# Pacman.net
KiCad netlist of a schematic drawn in EAGLE
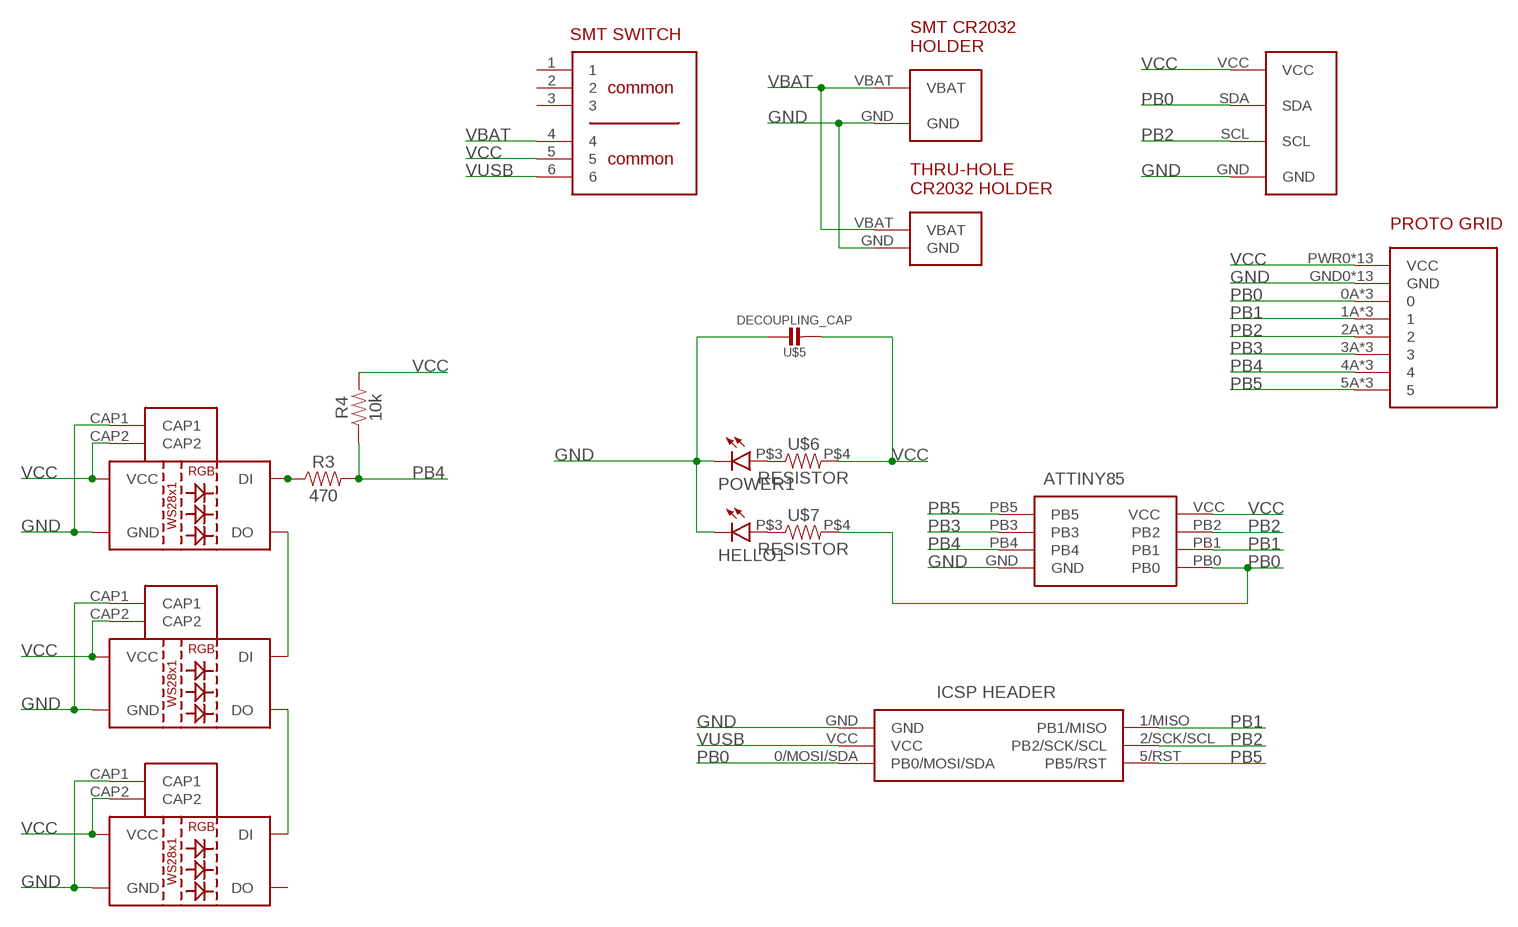
[diagram p0: schematic, sheet 1]

(export (version "E")
  (design (tool "Eeschema 10.0.6"))
  (components
    (comp (ref "D4")
      (value "WS2812B")
      (footprint "eagle-import:WS2812B")
      (libsource (lib "eagle-import") (part "WS2812B"))
    )
    (comp (ref "D5")
      (value "WS2812B")
      (footprint "eagle-import:WS2812B")
      (libsource (lib "eagle-import") (part "WS2812B"))
    )
    (comp (ref "D6")
      (value "WS2812B")
      (footprint "eagle-import:WS2812B")
      (libsource (lib "eagle-import") (part "WS2812B"))
    )
    (comp (ref "HELLO1")
      (value "LED3MM")
      (footprint "eagle-import:LED3MM")
      (libsource (lib "eagle-import") (part "LED3MM"))
    )
    (comp (ref "IC2")
      (value "ATTINY85-20SU")
      (footprint "eagle-import:SOT127P798X216-8N")
      (fields (field (name "RS_PART_NUMBER") "1331674"))
      (libsource (lib "eagle-import") (part "ATTINY85-20SU"))
    )
    (comp (ref "J2")
      (value "M20-9980346")
      (footprint "eagle-import:HDRV6W64P254_2X3_762X508X868P")
      (fields (field (name "RS_PART_NUMBER") "7457046P"))
      (libsource (lib "eagle-import") (part "M20-9980346"))
    )
    (comp (ref "POWER1")
      (value "LED3MM")
      (footprint "eagle-import:LED3MM")
      (libsource (lib "eagle-import") (part "LED3MM"))
    )
    (comp (ref "R3")
      (value "470")
      (footprint "eagle-import:0603")
      (libsource (lib "eagle-import") (part "470OHM-0603-1/10W-1%"))
    )
    (comp (ref "R4")
      (value "10k")
      (footprint "eagle-import:0603")
      (libsource (lib "eagle-import") (part "10KOHM-0603-1/10W-1%"))
    )
    (comp (ref "U$5")
      (value "DECOUPLING_CAP")
      (footprint "eagle-import:DECOUPLING_CAP")
      (libsource (lib "eagle-import") (part "DECOUPLING_CAP"))
    )
    (comp (ref "U$6")
      (value "RESISTOR")
      (footprint "eagle-import:AXIAL-0.3")
      (libsource (lib "eagle-import") (part "RESISTOR"))
    )
    (comp (ref "U$7")
      (value "RESISTOR")
      (footprint "eagle-import:AXIAL-0.3")
      (libsource (lib "eagle-import") (part "RESISTOR"))
    )
    (comp (ref "U$8")
      (value "SMT-SWITCH")
      (footprint "eagle-import:SMT-SWITCH")
      (libsource (lib "eagle-import") (part "SMT-SWITCH"))
    )
    (comp (ref "U$9")
      (value "PROTO")
      (footprint "eagle-import:PROTO")
      (libsource (lib "eagle-import") (part "PROTO"))
    )
    (comp (ref "U$10")
      (value "SMT-BATTERY-HOLDER")
      (footprint "eagle-import:SMT-CR-HOLDER")
      (libsource (lib "eagle-import") (part "SMT-BATTERY-HOLDER"))
    )
    (comp (ref "U$11")
      (value "THRU-CR-HOLDER")
      (footprint "eagle-import:THRU-CR-HOLDER")
      (libsource (lib "eagle-import") (part "THRU-CR-HOLDER"))
    )
    (comp (ref "U$12")
      (value "I2C-PADS")
      (footprint "eagle-import:I2C-PADS")
      (libsource (lib "eagle-import") (part "I2C-PADS"))
    )
  )
  (nets
    (net (code "1") (name "/GND") (class "Default")
      (node (ref "D4") (pin "CAP1") (pinfunction "CAP1_CAP1") (pintype "bidirectional"))
      (node (ref "D4") (pin "GND") (pinfunction "GND_GND") (pintype "bidirectional"))
      (node (ref "D5") (pin "CAP1") (pinfunction "CAP1_CAP1") (pintype "bidirectional"))
      (node (ref "D5") (pin "GND") (pinfunction "GND_GND") (pintype "bidirectional"))
      (node (ref "D6") (pin "CAP1") (pinfunction "CAP1_CAP1") (pintype "bidirectional"))
      (node (ref "D6") (pin "GND") (pinfunction "GND_GND") (pintype "bidirectional"))
      (node (ref "HELLO1") (pin "NEG") (pinfunction "NEG_NEG") (pintype "passive"))
      (node (ref "IC2") (pin "GND") (pinfunction "GND_GND") (pintype "bidirectional"))
      (node (ref "J2") (pin "GND") (pinfunction "GND_GND") (pintype "bidirectional"))
      (node (ref "POWER1") (pin "NEG") (pinfunction "NEG_NEG") (pintype "passive"))
      (node (ref "U$10") (pin "GND") (pinfunction "GND_GND") (pintype "bidirectional"))
      (node (ref "U$11") (pin "GND") (pinfunction "GND_GND") (pintype "bidirectional"))
      (node (ref "U$12") (pin "GND") (pinfunction "GND_GND") (pintype "bidirectional"))
      (node (ref "U$5") (pin "P$1") (pinfunction "1_P$1") (pintype "passive"))
      (node (ref "U$9") (pin "GND0") (pinfunction "GND_GND0") (pintype "bidirectional"))
      (node (ref "U$9") (pin "GND1") (pinfunction "GND_GND1") (pintype "bidirectional"))
      (node (ref "U$9") (pin "GND10") (pinfunction "GND_GND10") (pintype "bidirectional"))
      (node (ref "U$9") (pin "GND11") (pinfunction "GND_GND11") (pintype "bidirectional"))
      (node (ref "U$9") (pin "GND12") (pinfunction "GND_GND12") (pintype "bidirectional"))
      (node (ref "U$9") (pin "GND2") (pinfunction "GND_GND2") (pintype "bidirectional"))
      (node (ref "U$9") (pin "GND3") (pinfunction "GND_GND3") (pintype "bidirectional"))
      (node (ref "U$9") (pin "GND4") (pinfunction "GND_GND4") (pintype "bidirectional"))
      (node (ref "U$9") (pin "GND5") (pinfunction "GND_GND5") (pintype "bidirectional"))
      (node (ref "U$9") (pin "GND6") (pinfunction "GND_GND6") (pintype "bidirectional"))
      (node (ref "U$9") (pin "GND7") (pinfunction "GND_GND7") (pintype "bidirectional"))
      (node (ref "U$9") (pin "GND8") (pinfunction "GND_GND8") (pintype "bidirectional"))
      (node (ref "U$9") (pin "GND9") (pinfunction "GND_GND9") (pintype "bidirectional"))
    )
    (net (code "2") (name "/PB0") (class "Default")
      (node (ref "IC2") (pin "PB0") (pinfunction "PB0_PB0") (pintype "bidirectional"))
      (node (ref "J2") (pin "0/MOSI/SDA") (pinfunction "PB0/MOSI/SDA_0/MOSI/SDA") (pintype "bidirectional"))
      (node (ref "U$12") (pin "SDA") (pinfunction "SDA_SDA") (pintype "bidirectional"))
      (node (ref "U$7") (pin "P$4") (pinfunction "2_P$4") (pintype "passive"))
      (node (ref "U$9") (pin "0A") (pinfunction "0_0A") (pintype "bidirectional"))
      (node (ref "U$9") (pin "0B") (pinfunction "0_0B") (pintype "bidirectional"))
      (node (ref "U$9") (pin "0C") (pinfunction "0_0C") (pintype "bidirectional"))
    )
    (net (code "3") (name "/PB1") (class "Default")
      (node (ref "IC2") (pin "PB1") (pinfunction "PB1_PB1") (pintype "bidirectional"))
      (node (ref "J2") (pin "1/MISO") (pinfunction "PB1/MISO_1/MISO") (pintype "bidirectional"))
      (node (ref "U$9") (pin "1A") (pinfunction "1_1A") (pintype "bidirectional"))
      (node (ref "U$9") (pin "1B") (pinfunction "1_1B") (pintype "bidirectional"))
      (node (ref "U$9") (pin "1C") (pinfunction "1_1C") (pintype "bidirectional"))
    )
    (net (code "4") (name "/PB2") (class "Default")
      (node (ref "IC2") (pin "PB2") (pinfunction "PB2_PB2") (pintype "bidirectional"))
      (node (ref "J2") (pin "2/SCK/SCL") (pinfunction "PB2/SCK/SCL_2/SCK/SCL") (pintype "bidirectional"))
      (node (ref "U$12") (pin "SCL") (pinfunction "SCL_SCL") (pintype "bidirectional"))
      (node (ref "U$9") (pin "2A") (pinfunction "2_2A") (pintype "bidirectional"))
      (node (ref "U$9") (pin "2B") (pinfunction "2_2B") (pintype "bidirectional"))
      (node (ref "U$9") (pin "2C") (pinfunction "2_2C") (pintype "bidirectional"))
    )
    (net (code "5") (name "/PB3") (class "Default")
      (node (ref "IC2") (pin "PB3") (pinfunction "PB3_PB3") (pintype "bidirectional"))
      (node (ref "U$9") (pin "3A") (pinfunction "3_3A") (pintype "bidirectional"))
      (node (ref "U$9") (pin "3B") (pinfunction "3_3B") (pintype "bidirectional"))
      (node (ref "U$9") (pin "3C") (pinfunction "3_3C") (pintype "bidirectional"))
    )
    (net (code "6") (name "/PB4") (class "Default")
      (node (ref "IC2") (pin "PB4") (pinfunction "PB4_PB4") (pintype "bidirectional"))
      (node (ref "R3") (pin "2") (pinfunction "2_2") (pintype "passive"))
      (node (ref "R4") (pin "1") (pinfunction "1_1") (pintype "passive"))
      (node (ref "U$9") (pin "4A") (pinfunction "4_4A") (pintype "bidirectional"))
      (node (ref "U$9") (pin "4B") (pinfunction "4_4B") (pintype "bidirectional"))
      (node (ref "U$9") (pin "4C") (pinfunction "4_4C") (pintype "bidirectional"))
    )
    (net (code "7") (name "/PB5") (class "Default")
      (node (ref "IC2") (pin "PB5") (pinfunction "PB5_PB5") (pintype "bidirectional"))
      (node (ref "J2") (pin "5/RST") (pinfunction "PB5/RST_5/RST") (pintype "bidirectional"))
      (node (ref "U$9") (pin "5A") (pinfunction "5_5A") (pintype "bidirectional"))
      (node (ref "U$9") (pin "5B") (pinfunction "5_5B") (pintype "bidirectional"))
      (node (ref "U$9") (pin "5C") (pinfunction "5_5C") (pintype "bidirectional"))
    )
    (net (code "8") (name "/VBAT") (class "Default")
      (node (ref "U$10") (pin "VBAT") (pinfunction "VBAT_VBAT") (pintype "bidirectional"))
      (node (ref "U$11") (pin "VBAT") (pinfunction "VBAT_VBAT") (pintype "bidirectional"))
      (node (ref "U$8") (pin "4") (pinfunction "4_4") (pintype "bidirectional"))
    )
    (net (code "9") (name "/VCC") (class "Default")
      (node (ref "D4") (pin "CAP2") (pinfunction "CAP2_CAP2") (pintype "bidirectional"))
      (node (ref "D4") (pin "VCC") (pinfunction "VCC_VCC") (pintype "bidirectional"))
      (node (ref "D5") (pin "CAP2") (pinfunction "CAP2_CAP2") (pintype "bidirectional"))
      (node (ref "D5") (pin "VCC") (pinfunction "VCC_VCC") (pintype "bidirectional"))
      (node (ref "D6") (pin "CAP2") (pinfunction "CAP2_CAP2") (pintype "bidirectional"))
      (node (ref "D6") (pin "VCC") (pinfunction "VCC_VCC") (pintype "bidirectional"))
      (node (ref "IC2") (pin "VCC") (pinfunction "VCC_VCC") (pintype "bidirectional"))
      (node (ref "R4") (pin "2") (pinfunction "2_2") (pintype "passive"))
      (node (ref "U$12") (pin "VCC") (pinfunction "VCC_VCC") (pintype "bidirectional"))
      (node (ref "U$5") (pin "P$2") (pinfunction "2_P$2") (pintype "passive"))
      (node (ref "U$6") (pin "P$4") (pinfunction "2_P$4") (pintype "passive"))
      (node (ref "U$8") (pin "5") (pinfunction "5_5") (pintype "bidirectional"))
      (node (ref "U$9") (pin "PWR0") (pinfunction "VCC_PWR0") (pintype "bidirectional"))
      (node (ref "U$9") (pin "PWR1") (pinfunction "VCC_PWR1") (pintype "bidirectional"))
      (node (ref "U$9") (pin "PWR10") (pinfunction "VCC_PWR10") (pintype "bidirectional"))
      (node (ref "U$9") (pin "PWR11") (pinfunction "VCC_PWR11") (pintype "bidirectional"))
      (node (ref "U$9") (pin "PWR12") (pinfunction "VCC_PWR12") (pintype "bidirectional"))
      (node (ref "U$9") (pin "PWR2") (pinfunction "VCC_PWR2") (pintype "bidirectional"))
      (node (ref "U$9") (pin "PWR3") (pinfunction "VCC_PWR3") (pintype "bidirectional"))
      (node (ref "U$9") (pin "PWR4") (pinfunction "VCC_PWR4") (pintype "bidirectional"))
      (node (ref "U$9") (pin "PWR5") (pinfunction "VCC_PWR5") (pintype "bidirectional"))
      (node (ref "U$9") (pin "PWR6") (pinfunction "VCC_PWR6") (pintype "bidirectional"))
      (node (ref "U$9") (pin "PWR7") (pinfunction "VCC_PWR7") (pintype "bidirectional"))
      (node (ref "U$9") (pin "PWR8") (pinfunction "VCC_PWR8") (pintype "bidirectional"))
      (node (ref "U$9") (pin "PWR9") (pinfunction "VCC_PWR9") (pintype "bidirectional"))
    )
    (net (code "10") (name "/VUSB") (class "Default")
      (node (ref "J2") (pin "VCC") (pinfunction "VCC_VCC") (pintype "bidirectional"))
      (node (ref "U$8") (pin "6") (pinfunction "6_6") (pintype "bidirectional"))
    )
    (net (code "11") (name "Net-(D4-PadDI)") (class "Default")
      (node (ref "D4") (pin "DI") (pinfunction "DI_DI") (pintype "bidirectional"))
      (node (ref "R3") (pin "1") (pinfunction "1_1") (pintype "passive"))
    )
    (net (code "12") (name "Net-(D4-PadDO)") (class "Default")
      (node (ref "D4") (pin "DO") (pinfunction "DO_DO") (pintype "bidirectional"))
      (node (ref "D5") (pin "DI") (pinfunction "DI_DI") (pintype "bidirectional"))
    )
    (net (code "13") (name "Net-(D5-PadDO)") (class "Default")
      (node (ref "D5") (pin "DO") (pinfunction "DO_DO") (pintype "bidirectional"))
      (node (ref "D6") (pin "DI") (pinfunction "DI_DI") (pintype "bidirectional"))
    )
    (net (code "14") (name "Net-(U$6-1)") (class "Default")
      (node (ref "POWER1") (pin "POS") (pinfunction "POS_POS") (pintype "passive"))
      (node (ref "U$6") (pin "P$3") (pinfunction "1_P$3") (pintype "passive"))
    )
    (net (code "15") (name "Net-(U$7-1)") (class "Default")
      (node (ref "HELLO1") (pin "POS") (pinfunction "POS_POS") (pintype "passive"))
      (node (ref "U$7") (pin "P$3") (pinfunction "1_P$3") (pintype "passive"))
    )
    (net (code "16") (name "unconnected-(D6-PadDO)") (class "Default")
      (node (ref "D6") (pin "DO") (pinfunction "DO_DO") (pintype "bidirectional"))
    )
    (net (code "17") (name "unconnected-(U$8-Pad1)") (class "Default")
      (node (ref "U$8") (pin "1") (pinfunction "1_1") (pintype "bidirectional"))
    )
    (net (code "18") (name "unconnected-(U$8-Pad2)") (class "Default")
      (node (ref "U$8") (pin "2") (pinfunction "2_2") (pintype "bidirectional"))
    )
    (net (code "19") (name "unconnected-(U$8-Pad3)") (class "Default")
      (node (ref "U$8") (pin "3") (pinfunction "3_3") (pintype "bidirectional"))
    )
  )
)
